# microreg-sch.net
KiCad netlist of a schematic drawn in EAGLE
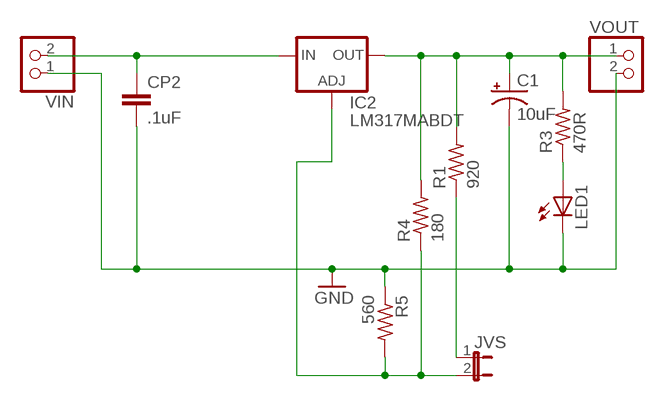
[diagram p0: schematic, sheet 1]

(export (version "E")
  (design (tool "Eeschema 10.0.6"))
  (components
    (comp (ref "C1")
      (value "10uF")
      (footprint "eagle-import:E2,5-5")
      (libsource (lib "eagle-import") (part "CPOL-USE2.5-5"))
    )
    (comp (ref "CP2")
      (value ".1uF")
      (footprint "eagle-import:C1206")
      (libsource (lib "eagle-import") (part "C-EUC1206"))
    )
    (comp (ref "IC2")
      (value "LM317MABDT")
      (footprint "eagle-import:DPACK")
      (libsource (lib "eagle-import") (part "v-reg_LM317?MABDT"))
    )
    (comp (ref "JVS")
      (value "JP1E")
      (footprint "eagle-import:JP1")
      (libsource (lib "eagle-import") (part "JP1E"))
    )
    (comp (ref "LED1")
      (value "LEDCHIPLED_1206")
      (footprint "eagle-import:CHIPLED_1206")
      (libsource (lib "eagle-import") (part "LEDCHIPLED_1206"))
    )
    (comp (ref "R1")
      (value "920")
      (footprint "eagle-import:R1206")
      (libsource (lib "eagle-import") (part "R-US_R1206"))
    )
    (comp (ref "R3")
      (value "470R")
      (footprint "eagle-import:M1206")
      (libsource (lib "eagle-import") (part "R-US_M1206"))
    )
    (comp (ref "R4")
      (value "180")
      (footprint "eagle-import:M1206")
      (libsource (lib "eagle-import") (part "R-US_M1206"))
    )
    (comp (ref "R5")
      (value "560")
      (footprint "eagle-import:M1206")
      (libsource (lib "eagle-import") (part "R-US_M1206"))
    )
    (comp (ref "VIN")
      (value "PINHD-1X2")
      (footprint "eagle-import:1X02")
      (libsource (lib "eagle-import") (part "PINHD-1X2"))
    )
    (comp (ref "VOUT")
      (value "PINHD-1X2")
      (footprint "eagle-import:1X02")
      (libsource (lib "eagle-import") (part "PINHD-1X2"))
    )
  )
  (nets
    (net (code "1") (name "GND") (class "Default")
      (node (ref "C1") (pin "-") (pinfunction "-_-") (pintype "passive"))
      (node (ref "CP2") (pin "2") (pinfunction "2_2") (pintype "passive"))
      (node (ref "LED1") (pin "C") (pinfunction "C_C") (pintype "passive"))
      (node (ref "R5") (pin "1") (pinfunction "1_1") (pintype "passive"))
      (node (ref "VIN") (pin "1") (pinfunction "1_1") (pintype "passive"))
      (node (ref "VOUT") (pin "2") (pinfunction "2_2") (pintype "passive"))
    )
    (net (code "2") (name "Net-(IC2-ADJ)") (class "Default")
      (node (ref "IC2") (pin "1") (pinfunction "ADJ_1") (pintype "input"))
      (node (ref "JVS") (pin "2") (pinfunction "2_2") (pintype "passive"))
      (node (ref "R4") (pin "1") (pinfunction "1_1") (pintype "passive"))
      (node (ref "R5") (pin "2") (pinfunction "2_2") (pintype "passive"))
    )
    (net (code "3") (name "Net-(IC2-IN)") (class "Default")
      (node (ref "CP2") (pin "1") (pinfunction "1_1") (pintype "passive"))
      (node (ref "IC2") (pin "3") (pinfunction "IN_3") (pintype "input"))
      (node (ref "VIN") (pin "2") (pinfunction "2_2") (pintype "passive"))
    )
    (net (code "4") (name "Net-(IC2-OUT)") (class "Default")
      (node (ref "C1") (pin "+") (pinfunction "+_+") (pintype "passive"))
      (node (ref "IC2") (pin "4") (pinfunction "OUT_4") (pintype "passive"))
      (node (ref "R1") (pin "2") (pinfunction "2_2") (pintype "passive"))
      (node (ref "R3") (pin "2") (pinfunction "2_2") (pintype "passive"))
      (node (ref "R4") (pin "2") (pinfunction "2_2") (pintype "passive"))
      (node (ref "VOUT") (pin "1") (pinfunction "1_1") (pintype "passive"))
    )
    (net (code "5") (name "Net-(JVS-Pad1)") (class "Default")
      (node (ref "JVS") (pin "1") (pinfunction "1_1") (pintype "passive"))
      (node (ref "R1") (pin "1") (pinfunction "1_1") (pintype "passive"))
    )
    (net (code "6") (name "Net-(LED1-PadA)") (class "Default")
      (node (ref "LED1") (pin "A") (pinfunction "A_A") (pintype "passive"))
      (node (ref "R3") (pin "1") (pinfunction "1_1") (pintype "passive"))
    )
  )
)
